# Timer-Ruler_v4.net
KiCad netlist of a schematic drawn in EAGLE
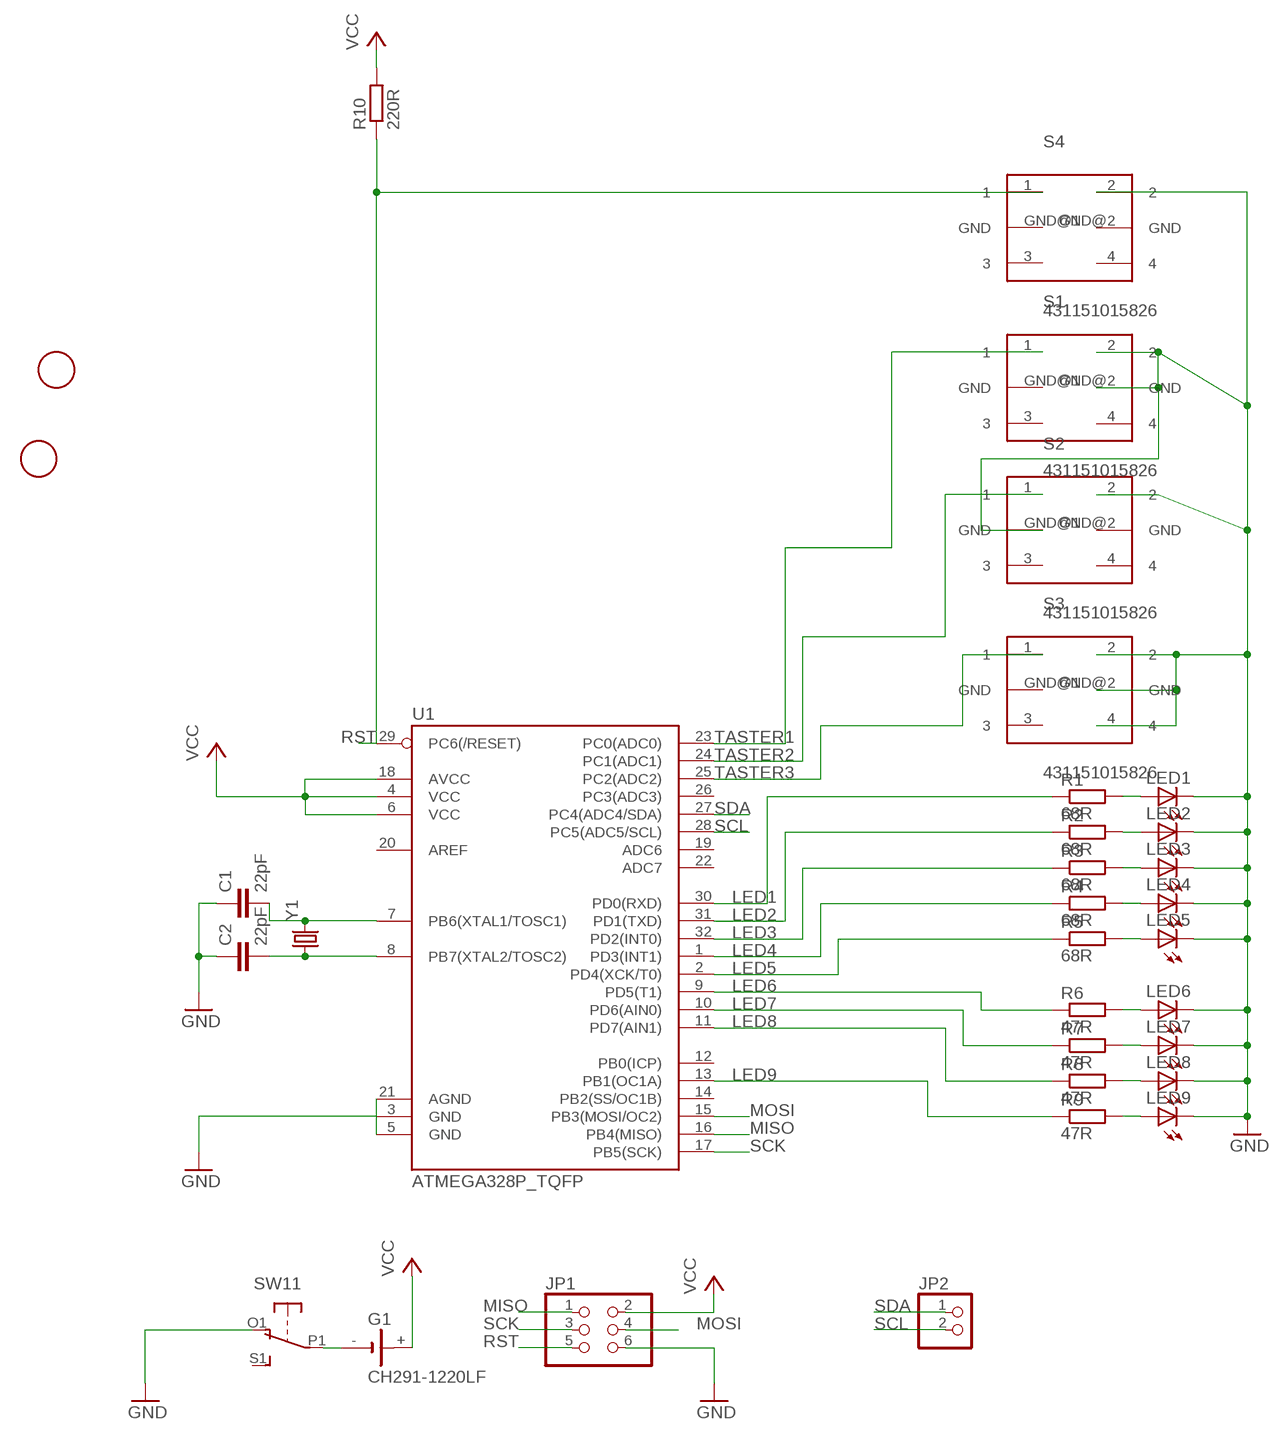
[diagram p0: schematic, sheet 1]

(export (version "E")
  (design (tool "Eeschema 10.0.6"))
  (components
    (comp (ref "C1")
      (value "22pF")
      (footprint "eagle-import:C0603")
      (libsource (lib "eagle-import") (part "C-EUC0603"))
    )
    (comp (ref "C2")
      (value "22pF")
      (footprint "eagle-import:C0603")
      (libsource (lib "eagle-import") (part "C-EUC0603"))
    )
    (comp (ref "G1")
      (value "CH291-1220LF")
      (footprint "eagle-import:CH291-1220LF")
      (libsource (lib "eagle-import") (part "CH291-1220LF"))
    )
    (comp (ref "JP1")
      (value "PINHD-2X3")
      (footprint "eagle-import:2X03")
      (libsource (lib "eagle-import") (part "PINHD-2X3"))
    )
    (comp (ref "JP2")
      (value "PINHD-1X2")
      (footprint "eagle-import:1X02")
      (libsource (lib "eagle-import") (part "PINHD-1X2"))
    )
    (comp (ref "LED1")
      (value "LEDCHIP-LED0603")
      (footprint "eagle-import:CHIP-LED0603")
      (libsource (lib "eagle-import") (part "LEDCHIP-LED0603"))
    )
    (comp (ref "LED2")
      (value "LEDCHIP-LED0603")
      (footprint "eagle-import:CHIP-LED0603")
      (libsource (lib "eagle-import") (part "LEDCHIP-LED0603"))
    )
    (comp (ref "LED3")
      (value "LEDCHIP-LED0603")
      (footprint "eagle-import:CHIP-LED0603")
      (libsource (lib "eagle-import") (part "LEDCHIP-LED0603"))
    )
    (comp (ref "LED4")
      (value "LEDCHIP-LED0603")
      (footprint "eagle-import:CHIP-LED0603")
      (libsource (lib "eagle-import") (part "LEDCHIP-LED0603"))
    )
    (comp (ref "LED5")
      (value "LEDCHIP-LED0603")
      (footprint "eagle-import:CHIP-LED0603")
      (libsource (lib "eagle-import") (part "LEDCHIP-LED0603"))
    )
    (comp (ref "LED6")
      (value "LEDCHIP-LED0603")
      (footprint "eagle-import:CHIP-LED0603")
      (libsource (lib "eagle-import") (part "LEDCHIP-LED0603"))
    )
    (comp (ref "LED7")
      (value "LEDCHIP-LED0603")
      (footprint "eagle-import:CHIP-LED0603")
      (libsource (lib "eagle-import") (part "LEDCHIP-LED0603"))
    )
    (comp (ref "LED8")
      (value "LEDCHIP-LED0603")
      (footprint "eagle-import:CHIP-LED0603")
      (libsource (lib "eagle-import") (part "LEDCHIP-LED0603"))
    )
    (comp (ref "LED9")
      (value "LEDCHIP-LED0603")
      (footprint "eagle-import:CHIP-LED0603")
      (libsource (lib "eagle-import") (part "LEDCHIP-LED0603"))
    )
    (comp (ref "R1")
      (value "68R")
      (footprint "eagle-import:R0603")
      (libsource (lib "eagle-import") (part "R-EU_R0603"))
    )
    (comp (ref "R2")
      (value "68R")
      (footprint "eagle-import:R0603")
      (libsource (lib "eagle-import") (part "R-EU_R0603"))
    )
    (comp (ref "R3")
      (value "68R")
      (footprint "eagle-import:R0603")
      (libsource (lib "eagle-import") (part "R-EU_R0603"))
    )
    (comp (ref "R4")
      (value "68R")
      (footprint "eagle-import:R0603")
      (libsource (lib "eagle-import") (part "R-EU_R0603"))
    )
    (comp (ref "R5")
      (value "68R")
      (footprint "eagle-import:R0603")
      (libsource (lib "eagle-import") (part "R-EU_R0603"))
    )
    (comp (ref "R6")
      (value "47R")
      (footprint "eagle-import:R0603")
      (libsource (lib "eagle-import") (part "R-EU_R0603"))
    )
    (comp (ref "R7")
      (value "47R")
      (footprint "eagle-import:R0603")
      (libsource (lib "eagle-import") (part "R-EU_R0603"))
    )
    (comp (ref "R8")
      (value "47R")
      (footprint "eagle-import:R0603")
      (libsource (lib "eagle-import") (part "R-EU_R0603"))
    )
    (comp (ref "R9")
      (value "47R")
      (footprint "eagle-import:R0603")
      (libsource (lib "eagle-import") (part "R-EU_R0603"))
    )
    (comp (ref "R10")
      (value "220R")
      (footprint "eagle-import:R0603")
      (libsource (lib "eagle-import") (part "R-EU_R0603"))
    )
    (comp (ref "S1")
      (value "431151015826")
      (footprint "eagle-import:431181015816")
      (libsource (lib "eagle-import") (part "431151015826"))
    )
    (comp (ref "S2")
      (value "431151015826")
      (footprint "eagle-import:431181015816")
      (libsource (lib "eagle-import") (part "431151015826"))
    )
    (comp (ref "S3")
      (value "431151015826")
      (footprint "eagle-import:431181015816")
      (libsource (lib "eagle-import") (part "431151015826"))
    )
    (comp (ref "S4")
      (value "431151015826")
      (footprint "eagle-import:431181015816")
      (libsource (lib "eagle-import") (part "431151015826"))
    )
    (comp (ref "SW1")
      (value "DPDT-EG1390")
      (footprint "eagle-import:EG1390")
      (libsource (lib "eagle-import") (part "DPDT-EG1390"))
    )
    (comp (ref "U$1")
      (value "FIDUCIAL")
      (footprint "eagle-import:FIDUCIAL_1MM")
      (libsource (lib "eagle-import") (part "FIDUCIAL"))
    )
    (comp (ref "U$2")
      (value "FIDUCIAL")
      (footprint "eagle-import:FIDUCIAL_1MM")
      (libsource (lib "eagle-import") (part "FIDUCIAL"))
    )
    (comp (ref "U1")
      (value "ATMEGA328P_TQFP")
      (footprint "eagle-import:TQFP32-08")
      (libsource (lib "eagle-import") (part "ATMEGA328P_TQFP"))
    )
    (comp (ref "Y1")
      (value "CRYSTALCRYSTAL-SMD-5X3-12.288MHZ")
      (footprint "eagle-import:CRYSTAL-SMD-5X3")
      (libsource (lib "eagle-import") (part "CRYSTALCRYSTAL-SMD-5X3-12.288MHZ"))
    )
  )
  (nets
    (net (code "1") (name "/LED1") (class "Default")
      (node (ref "R1") (pin "1") (pinfunction "1_1") (pintype "passive"))
      (node (ref "U1") (pin "30") (pinfunction "PD0(RXD)_30") (pintype "bidirectional"))
    )
    (net (code "2") (name "/LED2") (class "Default")
      (node (ref "R2") (pin "1") (pinfunction "1_1") (pintype "passive"))
      (node (ref "U1") (pin "31") (pinfunction "PD1(TXD)_31") (pintype "bidirectional"))
    )
    (net (code "3") (name "/LED3") (class "Default")
      (node (ref "R3") (pin "1") (pinfunction "1_1") (pintype "passive"))
      (node (ref "U1") (pin "32") (pinfunction "PD2(INT0)_32") (pintype "bidirectional"))
    )
    (net (code "4") (name "/LED4") (class "Default")
      (node (ref "R4") (pin "1") (pinfunction "1_1") (pintype "passive"))
      (node (ref "U1") (pin "1") (pinfunction "PD3(INT1)_1") (pintype "bidirectional"))
    )
    (net (code "5") (name "/LED5") (class "Default")
      (node (ref "R5") (pin "1") (pinfunction "1_1") (pintype "passive"))
      (node (ref "U1") (pin "2") (pinfunction "PD4(XCK/T0)_2") (pintype "bidirectional"))
    )
    (net (code "6") (name "/LED6") (class "Default")
      (node (ref "R6") (pin "1") (pinfunction "1_1") (pintype "passive"))
      (node (ref "U1") (pin "9") (pinfunction "PD5(T1)_9") (pintype "bidirectional"))
    )
    (net (code "7") (name "/LED7") (class "Default")
      (node (ref "R7") (pin "1") (pinfunction "1_1") (pintype "passive"))
      (node (ref "U1") (pin "10") (pinfunction "PD6(AIN0)_10") (pintype "bidirectional"))
    )
    (net (code "8") (name "/LED8") (class "Default")
      (node (ref "R8") (pin "1") (pinfunction "1_1") (pintype "passive"))
      (node (ref "U1") (pin "11") (pinfunction "PD7(AIN1)_11") (pintype "bidirectional"))
    )
    (net (code "9") (name "/LED9") (class "Default")
      (node (ref "R9") (pin "1") (pinfunction "1_1") (pintype "passive"))
      (node (ref "U1") (pin "13") (pinfunction "PB1(OC1A)_13") (pintype "bidirectional"))
    )
    (net (code "10") (name "/MISO") (class "Default")
      (node (ref "JP1") (pin "1") (pinfunction "1_1") (pintype "passive"))
      (node (ref "U1") (pin "16") (pinfunction "PB4(MISO)_16") (pintype "bidirectional"))
    )
    (net (code "11") (name "/MOSI") (class "Default")
      (node (ref "JP1") (pin "4") (pinfunction "4_4") (pintype "passive"))
      (node (ref "U1") (pin "15") (pinfunction "PB3(MOSI/OC2)_15") (pintype "bidirectional"))
    )
    (net (code "12") (name "/RST") (class "Default")
      (node (ref "JP1") (pin "5") (pinfunction "5_5") (pintype "passive"))
      (node (ref "R10") (pin "1") (pinfunction "1_1") (pintype "passive"))
      (node (ref "S4") (pin "1") (pinfunction "1_1") (pintype "bidirectional"))
      (node (ref "U1") (pin "29") (pinfunction "PC6(/RESET)_29") (pintype "bidirectional"))
    )
    (net (code "13") (name "/SCK") (class "Default")
      (node (ref "JP1") (pin "3") (pinfunction "3_3") (pintype "passive"))
      (node (ref "U1") (pin "17") (pinfunction "PB5(SCK)_17") (pintype "bidirectional"))
    )
    (net (code "14") (name "/SCL") (class "Default")
      (node (ref "JP2") (pin "2") (pinfunction "2_2") (pintype "passive"))
      (node (ref "U1") (pin "28") (pinfunction "PC5(ADC5/SCL)_28") (pintype "bidirectional"))
    )
    (net (code "15") (name "/SDA") (class "Default")
      (node (ref "JP2") (pin "1") (pinfunction "1_1") (pintype "passive"))
      (node (ref "U1") (pin "27") (pinfunction "PC4(ADC4/SDA)_27") (pintype "bidirectional"))
    )
    (net (code "16") (name "/TASTER1") (class "Default")
      (node (ref "S1") (pin "1") (pinfunction "1_1") (pintype "bidirectional"))
      (node (ref "U1") (pin "23") (pinfunction "PC0(ADC0)_23") (pintype "bidirectional"))
    )
    (net (code "17") (name "/TASTER2") (class "Default")
      (node (ref "S2") (pin "1") (pinfunction "1_1") (pintype "bidirectional"))
      (node (ref "U1") (pin "24") (pinfunction "PC1(ADC1)_24") (pintype "bidirectional"))
    )
    (net (code "18") (name "/TASTER3") (class "Default")
      (node (ref "S3") (pin "1") (pinfunction "1_1") (pintype "bidirectional"))
      (node (ref "U1") (pin "25") (pinfunction "PC2(ADC2)_25") (pintype "bidirectional"))
    )
    (net (code "19") (name "GND") (class "Default")
      (node (ref "C1") (pin "1") (pinfunction "1_1") (pintype "passive"))
      (node (ref "C2") (pin "1") (pinfunction "1_1") (pintype "passive"))
      (node (ref "JP1") (pin "6") (pinfunction "6_6") (pintype "passive"))
      (node (ref "LED1") (pin "C") (pinfunction "C_C") (pintype "passive"))
      (node (ref "LED2") (pin "C") (pinfunction "C_C") (pintype "passive"))
      (node (ref "LED3") (pin "C") (pinfunction "C_C") (pintype "passive"))
      (node (ref "LED4") (pin "C") (pinfunction "C_C") (pintype "passive"))
      (node (ref "LED5") (pin "C") (pinfunction "C_C") (pintype "passive"))
      (node (ref "LED6") (pin "C") (pinfunction "C_C") (pintype "passive"))
      (node (ref "LED7") (pin "C") (pinfunction "C_C") (pintype "passive"))
      (node (ref "LED8") (pin "C") (pinfunction "C_C") (pintype "passive"))
      (node (ref "LED9") (pin "C") (pinfunction "C_C") (pintype "passive"))
      (node (ref "S1") (pin "2") (pinfunction "2_2") (pintype "bidirectional"))
      (node (ref "S1") (pin "GND@2") (pinfunction "GND_GND@2") (pintype "bidirectional"))
      (node (ref "S2") (pin "2") (pinfunction "2_2") (pintype "bidirectional"))
      (node (ref "S2") (pin "GND@1") (pinfunction "GND_GND@1") (pintype "bidirectional"))
      (node (ref "S3") (pin "2") (pinfunction "2_2") (pintype "bidirectional"))
      (node (ref "S3") (pin "4") (pinfunction "4_4") (pintype "bidirectional"))
      (node (ref "S3") (pin "GND@2") (pinfunction "GND_GND@2") (pintype "bidirectional"))
      (node (ref "S4") (pin "2") (pinfunction "2_2") (pintype "bidirectional"))
      (node (ref "SW1") (pin "O1") (pinfunction "O_O1") (pintype "passive"))
      (node (ref "U1") (pin "3") (pinfunction "GND_3") (pintype "bidirectional"))
    )
    (net (code "20") (name "Net-(LED1-PadA)") (class "Default")
      (node (ref "LED1") (pin "A") (pinfunction "A_A") (pintype "passive"))
      (node (ref "R1") (pin "2") (pinfunction "2_2") (pintype "passive"))
    )
    (net (code "21") (name "Net-(LED2-PadA)") (class "Default")
      (node (ref "LED2") (pin "A") (pinfunction "A_A") (pintype "passive"))
      (node (ref "R2") (pin "2") (pinfunction "2_2") (pintype "passive"))
    )
    (net (code "22") (name "Net-(LED3-PadA)") (class "Default")
      (node (ref "LED3") (pin "A") (pinfunction "A_A") (pintype "passive"))
      (node (ref "R3") (pin "2") (pinfunction "2_2") (pintype "passive"))
    )
    (net (code "23") (name "Net-(LED4-PadA)") (class "Default")
      (node (ref "LED4") (pin "A") (pinfunction "A_A") (pintype "passive"))
      (node (ref "R4") (pin "2") (pinfunction "2_2") (pintype "passive"))
    )
    (net (code "24") (name "Net-(LED5-PadA)") (class "Default")
      (node (ref "LED5") (pin "A") (pinfunction "A_A") (pintype "passive"))
      (node (ref "R5") (pin "2") (pinfunction "2_2") (pintype "passive"))
    )
    (net (code "25") (name "Net-(LED6-PadA)") (class "Default")
      (node (ref "LED6") (pin "A") (pinfunction "A_A") (pintype "passive"))
      (node (ref "R6") (pin "2") (pinfunction "2_2") (pintype "passive"))
    )
    (net (code "26") (name "Net-(LED7-PadA)") (class "Default")
      (node (ref "LED7") (pin "A") (pinfunction "A_A") (pintype "passive"))
      (node (ref "R7") (pin "2") (pinfunction "2_2") (pintype "passive"))
    )
    (net (code "27") (name "Net-(LED8-PadA)") (class "Default")
      (node (ref "LED8") (pin "A") (pinfunction "A_A") (pintype "passive"))
      (node (ref "R8") (pin "2") (pinfunction "2_2") (pintype "passive"))
    )
    (net (code "28") (name "Net-(LED9-PadA)") (class "Default")
      (node (ref "LED9") (pin "A") (pinfunction "A_A") (pintype "passive"))
      (node (ref "R9") (pin "2") (pinfunction "2_2") (pintype "passive"))
    )
    (net (code "29") (name "Net-(SW1A-P)") (class "Default")
      (node (ref "G1") (pin "-") (pinfunction "-_-") (pintype "passive"))
      (node (ref "SW1") (pin "P1") (pinfunction "P_P1") (pintype "passive"))
    )
    (net (code "30") (name "Net-(U1-AGND)") (class "Default")
      (node (ref "U1") (pin "21") (pinfunction "AGND_21") (pintype "bidirectional"))
      (node (ref "U1") (pin "5") (pinfunction "GND_5") (pintype "bidirectional"))
    )
    (net (code "31") (name "Net-(U1-PB6(XTAL1{slash}TOSC1))") (class "Default")
      (node (ref "C1") (pin "2") (pinfunction "2_2") (pintype "passive"))
      (node (ref "U1") (pin "7") (pinfunction "PB6(XTAL1/TOSC1)_7") (pintype "bidirectional"))
      (node (ref "Y1") (pin "3") (pinfunction "2_3") (pintype "passive"))
    )
    (net (code "32") (name "Net-(U1-PB7(XTAL2{slash}TOSC2))") (class "Default")
      (node (ref "C2") (pin "2") (pinfunction "2_2") (pintype "passive"))
      (node (ref "U1") (pin "8") (pinfunction "PB7(XTAL2/TOSC2)_8") (pintype "bidirectional"))
      (node (ref "Y1") (pin "1") (pinfunction "1_1") (pintype "passive"))
    )
    (net (code "33") (name "VCC") (class "Default")
      (node (ref "G1") (pin "+") (pinfunction "+_+") (pintype "passive"))
      (node (ref "JP1") (pin "2") (pinfunction "2_2") (pintype "passive"))
      (node (ref "R10") (pin "2") (pinfunction "2_2") (pintype "passive"))
      (node (ref "U1") (pin "18") (pinfunction "AVCC_18") (pintype "bidirectional"))
      (node (ref "U1") (pin "4") (pinfunction "VCC_4") (pintype "bidirectional"))
      (node (ref "U1") (pin "6") (pinfunction "VCC_6") (pintype "bidirectional"))
    )
    (net (code "34") (name "unconnected-(S1-GND-PadGND@1)") (class "Default")
      (node (ref "S1") (pin "GND@1") (pinfunction "GND_GND@1") (pintype "bidirectional"))
    )
    (net (code "35") (name "unconnected-(S1-Pad3)") (class "Default")
      (node (ref "S1") (pin "3") (pinfunction "3_3") (pintype "bidirectional"))
    )
    (net (code "36") (name "unconnected-(S1-Pad4)") (class "Default")
      (node (ref "S1") (pin "4") (pinfunction "4_4") (pintype "bidirectional"))
    )
    (net (code "37") (name "unconnected-(S2-GND-PadGND@2)") (class "Default")
      (node (ref "S2") (pin "GND@2") (pinfunction "GND_GND@2") (pintype "bidirectional"))
    )
    (net (code "38") (name "unconnected-(S2-Pad3)") (class "Default")
      (node (ref "S2") (pin "3") (pinfunction "3_3") (pintype "bidirectional"))
    )
    (net (code "39") (name "unconnected-(S2-Pad4)") (class "Default")
      (node (ref "S2") (pin "4") (pinfunction "4_4") (pintype "bidirectional"))
    )
    (net (code "40") (name "unconnected-(S3-GND-PadGND@1)") (class "Default")
      (node (ref "S3") (pin "GND@1") (pinfunction "GND_GND@1") (pintype "bidirectional"))
    )
    (net (code "41") (name "unconnected-(S3-Pad3)") (class "Default")
      (node (ref "S3") (pin "3") (pinfunction "3_3") (pintype "bidirectional"))
    )
    (net (code "42") (name "unconnected-(S4-GND-PadGND@1)") (class "Default")
      (node (ref "S4") (pin "GND@1") (pinfunction "GND_GND@1") (pintype "bidirectional"))
    )
    (net (code "43") (name "unconnected-(S4-GND-PadGND@2)") (class "Default")
      (node (ref "S4") (pin "GND@2") (pinfunction "GND_GND@2") (pintype "bidirectional"))
    )
    (net (code "44") (name "unconnected-(S4-Pad3)") (class "Default")
      (node (ref "S4") (pin "3") (pinfunction "3_3") (pintype "bidirectional"))
    )
    (net (code "45") (name "unconnected-(S4-Pad4)") (class "Default")
      (node (ref "S4") (pin "4") (pinfunction "4_4") (pintype "bidirectional"))
    )
    (net (code "46") (name "unconnected-(SW1A-S-PadS1)") (class "Default")
      (node (ref "SW1") (pin "S1") (pinfunction "S_S1") (pintype "passive"))
    )
    (net (code "47") (name "unconnected-(U1-ADC6-Pad19)") (class "Default")
      (node (ref "U1") (pin "19") (pinfunction "ADC6_19") (pintype "bidirectional"))
    )
    (net (code "48") (name "unconnected-(U1-ADC7-Pad22)") (class "Default")
      (node (ref "U1") (pin "22") (pinfunction "ADC7_22") (pintype "bidirectional"))
    )
    (net (code "49") (name "unconnected-(U1-AREF-Pad20)") (class "Default")
      (node (ref "U1") (pin "20") (pinfunction "AREF_20") (pintype "bidirectional"))
    )
    (net (code "50") (name "unconnected-(U1-PB0(ICP)-Pad12)") (class "Default")
      (node (ref "U1") (pin "12") (pinfunction "PB0(ICP)_12") (pintype "bidirectional"))
    )
    (net (code "51") (name "unconnected-(U1-PB2(SS{slash}OC1B)-Pad14)") (class "Default")
      (node (ref "U1") (pin "14") (pinfunction "PB2(SS/OC1B)_14") (pintype "bidirectional"))
    )
    (net (code "52") (name "unconnected-(U1-PC3(ADC3)-Pad26)") (class "Default")
      (node (ref "U1") (pin "26") (pinfunction "PC3(ADC3)_26") (pintype "bidirectional"))
    )
  )
)
